# ESC2.net
KiCad netlist of a schematic drawn in Altium Designer
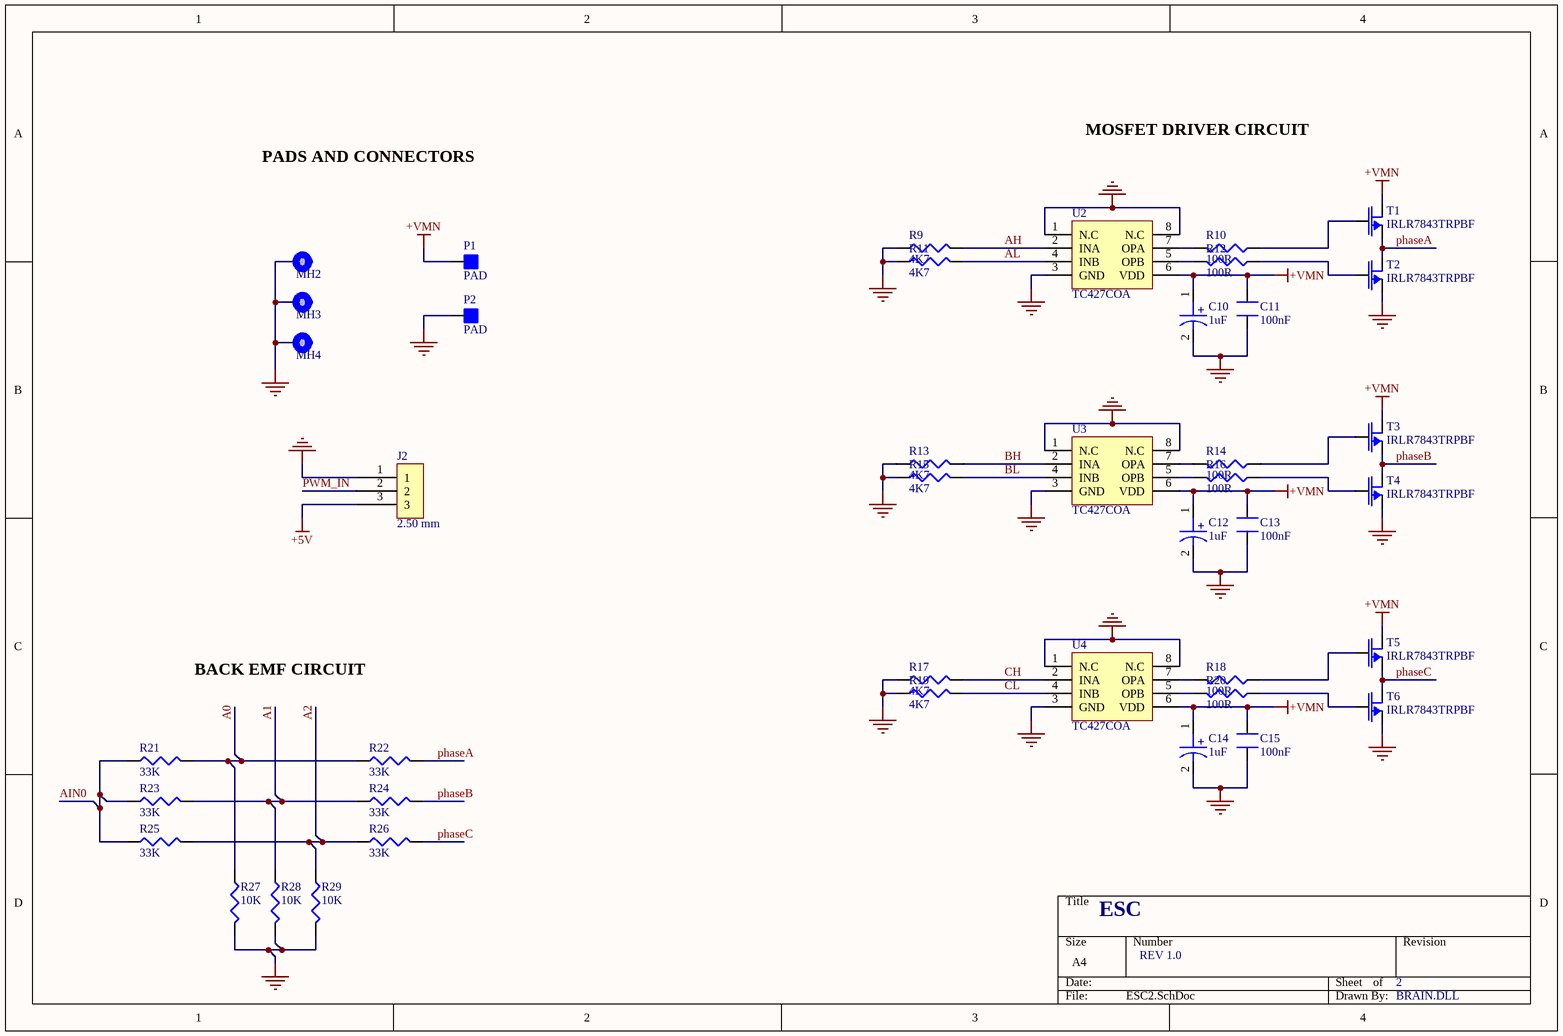
[diagram p0: ESC2.SchDoc]

(export (version "E")
  (design (tool "Eeschema 10.0.6"))
  (components
    (comp (ref "C10")
      (value "1uF")
      (footprint "1206 TANTAL CAP")
      (description "Cap Tant Solid 1uF 35V A CASE 10% (3.2 X 1.6 X 1.6mm) SMD 3216-18 7.5 Ohm 125 C T/R")
      (fields
        (field (name "MANUFACTURER") "KEMET")
        (field (name "MANUFACTURER PART NUMBER") "T491A105K035AT")
      )
      (libsource (lib "ESClib1") (part "T491A105K035AT"))
    )
    (comp (ref "C11")
      (value "100nF")
      (footprint "Z0603")
      (description "Multi Layer Ceramic Capacitor (MLCC) / Cap Ceramic 0.1uF 50V X7R 10% Pad SMD 0603 125°C T/R")
      (fields
        (field (name "MANUFACTURER") "Samsung")
        (field (name "MANUFACTURER PART NUMBER") "CL10B104KB8NNNC")
      )
      (libsource (lib "ESClib1") (part "CL10B104KB8NNNC"))
    )
    (comp (ref "C12")
      (value "1uF")
      (footprint "1206 TANTAL CAP")
      (description "Cap Tant Solid 1uF 35V A CASE 10% (3.2 X 1.6 X 1.6mm) SMD 3216-18 7.5 Ohm 125 C T/R")
      (fields
        (field (name "MANUFACTURER") "KEMET")
        (field (name "MANUFACTURER PART NUMBER") "T491A105K035AT")
      )
      (libsource (lib "ESClib1") (part "T491A105K035AT"))
    )
    (comp (ref "C13")
      (value "100nF")
      (footprint "Z0603")
      (description "Multi Layer Ceramic Capacitor (MLCC) / Cap Ceramic 0.1uF 50V X7R 10% Pad SMD 0603 125°C T/R")
      (fields
        (field (name "MANUFACTURER") "Samsung")
        (field (name "MANUFACTURER PART NUMBER") "CL10B104KB8NNNC")
      )
      (libsource (lib "ESClib1") (part "CL10B104KB8NNNC"))
    )
    (comp (ref "C14")
      (value "1uF")
      (footprint "1206 TANTAL CAP")
      (description "Cap Tant Solid 1uF 35V A CASE 10% (3.2 X 1.6 X 1.6mm) SMD 3216-18 7.5 Ohm 125 C T/R")
      (fields
        (field (name "MANUFACTURER") "KEMET")
        (field (name "MANUFACTURER PART NUMBER") "T491A105K035AT")
      )
      (libsource (lib "ESClib1") (part "T491A105K035AT"))
    )
    (comp (ref "C15")
      (value "100nF")
      (footprint "Z0603")
      (description "Multi Layer Ceramic Capacitor (MLCC) / Cap Ceramic 0.1uF 50V X7R 10% Pad SMD 0603 125°C T/R")
      (fields
        (field (name "MANUFACTURER") "Samsung")
        (field (name "MANUFACTURER PART NUMBER") "CL10B104KB8NNNC")
      )
      (libsource (lib "ESClib1") (part "CL10B104KB8NNNC"))
    )
    (comp (ref "J2")
      (value "2.50 mm")
      (footprint "L-KLS1-XL4-2.50-03-R")
      (libsource (lib "ESClib1") (part "L-KLS1-XL4-2.50-03-R"))
    )
    (comp (ref "MH2")
      (value "MH_7.4MMC_3.2MMD")
      (footprint "MH_7.4MMC_3.2MMD_NON_COPPER_NPLT")
      (description "Mounting Hole 7.4 mm Diameter (Non Copper), 3.2 mm Drill NPTH")
      (libsource (lib "ESClib1") (part "MH_7.4MMNC_3.2MMD"))
    )
    (comp (ref "MH3")
      (value "MH_7.4MMC_3.2MMD")
      (footprint "MH_7.4MMC_3.2MMD_NON_COPPER_NPLT")
      (description "Mounting Hole 7.4 mm Diameter (Non Copper), 3.2 mm Drill NPTH")
      (libsource (lib "ESClib1") (part "MH_7.4MMNC_3.2MMD"))
    )
    (comp (ref "MH4")
      (value "MH_7.4MMC_3.2MMD")
      (footprint "MH_7.4MMC_3.2MMD_NON_COPPER_NPLT")
      (description "Mounting Hole 7.4 mm Diameter (Non Copper), 3.2 mm Drill NPTH")
      (libsource (lib "ESClib1") (part "MH_7.4MMNC_3.2MMD"))
    )
    (comp (ref "P1") (value "PAD") (footprint "SQARE_PAD") (libsource (lib "ESClib1") (part "SQARE_PAD")))
    (comp (ref "P2") (value "PAD") (footprint "SQARE_PAD") (libsource (lib "ESClib1") (part "SQARE_PAD")))
    (comp (ref "R9")
      (value "4K7")
      (footprint "Z0603")
      (fields
        (field (name "MANUFACTURER") "Multicomp")
        (field (name "MANUFACTURER PART NUMBER") "MC0603SAF4701T5E")
        (field (name "TOLERANCE") "1%")
      )
      (libsource (lib "ESClib1") (part "MC0603SAF4701T5E"))
    )
    (comp (ref "R10") (value "100R") (footprint "Z0603") (libsource (lib "ESClib1") (part "0603SAJ0101T5E")))
    (comp (ref "R11")
      (value "4K7")
      (footprint "Z0603")
      (fields
        (field (name "MANUFACTURER") "Multicomp")
        (field (name "MANUFACTURER PART NUMBER") "MC0603SAF4701T5E")
        (field (name "TOLERANCE") "1%")
      )
      (libsource (lib "ESClib1") (part "MC0603SAF4701T5E"))
    )
    (comp (ref "R12") (value "100R") (footprint "Z0603") (libsource (lib "ESClib1") (part "0603SAJ0101T5E")))
    (comp (ref "R13")
      (value "4K7")
      (footprint "Z0603")
      (fields
        (field (name "MANUFACTURER") "Multicomp")
        (field (name "MANUFACTURER PART NUMBER") "MC0603SAF4701T5E")
        (field (name "TOLERANCE") "1%")
      )
      (libsource (lib "ESClib1") (part "MC0603SAF4701T5E"))
    )
    (comp (ref "R14") (value "100R") (footprint "Z0603") (libsource (lib "ESClib1") (part "0603SAJ0101T5E")))
    (comp (ref "R15")
      (value "4K7")
      (footprint "Z0603")
      (fields
        (field (name "MANUFACTURER") "Multicomp")
        (field (name "MANUFACTURER PART NUMBER") "MC0603SAF4701T5E")
        (field (name "TOLERANCE") "1%")
      )
      (libsource (lib "ESClib1") (part "MC0603SAF4701T5E"))
    )
    (comp (ref "R16") (value "100R") (footprint "Z0603") (libsource (lib "ESClib1") (part "0603SAJ0101T5E")))
    (comp (ref "R17")
      (value "4K7")
      (footprint "Z0603")
      (fields
        (field (name "MANUFACTURER") "Multicomp")
        (field (name "MANUFACTURER PART NUMBER") "MC0603SAF4701T5E")
        (field (name "TOLERANCE") "1%")
      )
      (libsource (lib "ESClib1") (part "MC0603SAF4701T5E"))
    )
    (comp (ref "R18") (value "100R") (footprint "Z0603") (libsource (lib "ESClib1") (part "0603SAJ0101T5E")))
    (comp (ref "R19")
      (value "4K7")
      (footprint "Z0603")
      (fields
        (field (name "MANUFACTURER") "Multicomp")
        (field (name "MANUFACTURER PART NUMBER") "MC0603SAF4701T5E")
        (field (name "TOLERANCE") "1%")
      )
      (libsource (lib "ESClib1") (part "MC0603SAF4701T5E"))
    )
    (comp (ref "R20") (value "100R") (footprint "Z0603") (libsource (lib "ESClib1") (part "0603SAJ0101T5E")))
    (comp (ref "R21") (value "33K") (footprint "Z0603") (libsource (lib "ESClib1") (part "RI0603L3302FT")))
    (comp (ref "R22") (value "33K") (footprint "Z0603") (libsource (lib "ESClib1") (part "RI0603L3302FT")))
    (comp (ref "R23") (value "33K") (footprint "Z0603") (libsource (lib "ESClib1") (part "RI0603L3302FT")))
    (comp (ref "R24") (value "33K") (footprint "Z0603") (libsource (lib "ESClib1") (part "RI0603L3302FT")))
    (comp (ref "R25") (value "33K") (footprint "Z0603") (libsource (lib "ESClib1") (part "RI0603L3302FT")))
    (comp (ref "R26") (value "33K") (footprint "Z0603") (libsource (lib "ESClib1") (part "RI0603L3302FT")))
    (comp (ref "R27") (value "10K") (footprint "Z0603") (libsource (lib "ESClib1") (part "CQ03SAF1002T5E")))
    (comp (ref "R28") (value "10K") (footprint "Z0603") (libsource (lib "ESClib1") (part "CQ03SAF1002T5E")))
    (comp (ref "R29") (value "10K") (footprint "Z0603") (libsource (lib "ESClib1") (part "CQ03SAF1002T5E")))
    (comp (ref "T1")
      (value "IRLR7843TRPBF")
      (footprint "TO-252-3")
      (description "MOSFET, 30V, 161A, 3.3 mOhm, 34 nC Qg, Logic Level, D-Pak")
      (fields (field (name "MANUFACTURER") "International Rectifier"))
      (libsource (lib "ESClib1") (part "IRLR7843TRPBF"))
    )
    (comp (ref "T2")
      (value "IRLR7843TRPBF")
      (footprint "TO-252-3")
      (description "MOSFET, 30V, 161A, 3.3 mOhm, 34 nC Qg, Logic Level, D-Pak")
      (fields (field (name "MANUFACTURER") "International Rectifier"))
      (libsource (lib "ESClib1") (part "IRLR7843TRPBF"))
    )
    (comp (ref "T3")
      (value "IRLR7843TRPBF")
      (footprint "TO-252-3")
      (description "MOSFET, 30V, 161A, 3.3 mOhm, 34 nC Qg, Logic Level, D-Pak")
      (fields (field (name "MANUFACTURER") "International Rectifier"))
      (libsource (lib "ESClib1") (part "IRLR7843TRPBF"))
    )
    (comp (ref "T4")
      (value "IRLR7843TRPBF")
      (footprint "TO-252-3")
      (description "MOSFET, 30V, 161A, 3.3 mOhm, 34 nC Qg, Logic Level, D-Pak")
      (fields (field (name "MANUFACTURER") "International Rectifier"))
      (libsource (lib "ESClib1") (part "IRLR7843TRPBF"))
    )
    (comp (ref "T5")
      (value "IRLR7843TRPBF")
      (footprint "TO-252-3")
      (description "MOSFET, 30V, 161A, 3.3 mOhm, 34 nC Qg, Logic Level, D-Pak")
      (fields (field (name "MANUFACTURER") "International Rectifier"))
      (libsource (lib "ESClib1") (part "IRLR7843TRPBF"))
    )
    (comp (ref "T6")
      (value "IRLR7843TRPBF")
      (footprint "TO-252-3")
      (description "MOSFET, 30V, 161A, 3.3 mOhm, 34 nC Qg, Logic Level, D-Pak")
      (fields (field (name "MANUFACTURER") "International Rectifier"))
      (libsource (lib "ESClib1") (part "IRLR7843TRPBF"))
    )
    (comp (ref "U2")
      (value "TC427COA")
      (footprint "SOIC-8")
      (description "IC MOSFET DVR 1.5A DUAL HS 8SOIC")
      (fields (field (name "MANUFACTURER") "Microchip"))
      (libsource (lib "ESClib1") (part "TC427COA"))
    )
    (comp (ref "U3")
      (value "TC427COA")
      (footprint "SOIC-8")
      (description "IC MOSFET DVR 1.5A DUAL HS 8SOIC")
      (fields (field (name "MANUFACTURER") "Microchip"))
      (libsource (lib "ESClib1") (part "TC427COA"))
    )
    (comp (ref "U4")
      (value "TC427COA")
      (footprint "SOIC-8")
      (description "IC MOSFET DVR 1.5A DUAL HS 8SOIC")
      (fields (field (name "MANUFACTURER") "Microchip"))
      (libsource (lib "ESClib1") (part "TC427COA"))
    )
  )
  (nets
    (net (code "1") (name "+5V") (class "Default")
      (node (ref "J2") (pin "3") (pinfunction "3_3") (pintype "passive"))
    )
    (net (code "2") (name "+VMN") (class "Default")
      (node (ref "C10") (pin "1") (pinfunction "1_1") (pintype "passive"))
      (node (ref "C11") (pin "1") (pinfunction "1_1") (pintype "passive"))
      (node (ref "C12") (pin "1") (pinfunction "1_1") (pintype "passive"))
      (node (ref "C13") (pin "1") (pinfunction "1_1") (pintype "passive"))
      (node (ref "C14") (pin "1") (pinfunction "1_1") (pintype "passive"))
      (node (ref "C15") (pin "1") (pinfunction "1_1") (pintype "passive"))
      (node (ref "P1") (pin "1") (pinfunction "1_1") (pintype "passive"))
      (node (ref "T1") (pin "2") (pinfunction "DRAIN_2") (pintype "passive"))
      (node (ref "T3") (pin "2") (pinfunction "DRAIN_2") (pintype "passive"))
      (node (ref "T5") (pin "2") (pinfunction "DRAIN_2") (pintype "passive"))
      (node (ref "U2") (pin "6") (pinfunction "VDD_6") (pintype "passive"))
      (node (ref "U3") (pin "6") (pinfunction "VDD_6") (pintype "passive"))
      (node (ref "U4") (pin "6") (pinfunction "VDD_6") (pintype "passive"))
    )
    (net (code "3") (name "/A0") (class "Default")
      (node (ref "R21") (pin "2") (pinfunction "2_2") (pintype "passive"))
      (node (ref "R22") (pin "1") (pinfunction "1_1") (pintype "passive"))
      (node (ref "R27") (pin "1") (pinfunction "1_1") (pintype "passive"))
    )
    (net (code "4") (name "/A1") (class "Default")
      (node (ref "R23") (pin "2") (pinfunction "2_2") (pintype "passive"))
      (node (ref "R24") (pin "1") (pinfunction "1_1") (pintype "passive"))
      (node (ref "R28") (pin "1") (pinfunction "1_1") (pintype "passive"))
    )
    (net (code "5") (name "/A2") (class "Default")
      (node (ref "R25") (pin "2") (pinfunction "2_2") (pintype "passive"))
      (node (ref "R26") (pin "1") (pinfunction "1_1") (pintype "passive"))
      (node (ref "R29") (pin "1") (pinfunction "1_1") (pintype "passive"))
    )
    (net (code "6") (name "/AH") (class "Default")
      (node (ref "R9") (pin "2") (pinfunction "2_2") (pintype "passive"))
      (node (ref "U2") (pin "2") (pinfunction "INA_2") (pintype "passive"))
    )
    (net (code "7") (name "/AIN0") (class "Default")
      (node (ref "R21") (pin "1") (pinfunction "1_1") (pintype "passive"))
      (node (ref "R23") (pin "1") (pinfunction "1_1") (pintype "passive"))
      (node (ref "R25") (pin "1") (pinfunction "1_1") (pintype "passive"))
    )
    (net (code "8") (name "/AL") (class "Default")
      (node (ref "R11") (pin "2") (pinfunction "2_2") (pintype "passive"))
      (node (ref "U2") (pin "4") (pinfunction "INB_4") (pintype "passive"))
    )
    (net (code "9") (name "/BH") (class "Default")
      (node (ref "R13") (pin "2") (pinfunction "2_2") (pintype "passive"))
      (node (ref "U3") (pin "2") (pinfunction "INA_2") (pintype "passive"))
    )
    (net (code "10") (name "/BL") (class "Default")
      (node (ref "R15") (pin "2") (pinfunction "2_2") (pintype "passive"))
      (node (ref "U3") (pin "4") (pinfunction "INB_4") (pintype "passive"))
    )
    (net (code "11") (name "/CH") (class "Default")
      (node (ref "R17") (pin "2") (pinfunction "2_2") (pintype "passive"))
      (node (ref "U4") (pin "2") (pinfunction "INA_2") (pintype "passive"))
    )
    (net (code "12") (name "/CL") (class "Default")
      (node (ref "R19") (pin "2") (pinfunction "2_2") (pintype "passive"))
      (node (ref "U4") (pin "4") (pinfunction "INB_4") (pintype "passive"))
    )
    (net (code "13") (name "/PWM_IN") (class "Default")
      (node (ref "J2") (pin "2") (pinfunction "2_2") (pintype "passive"))
    )
    (net (code "14") (name "/phaseA") (class "Default")
      (node (ref "R22") (pin "2") (pinfunction "2_2") (pintype "passive"))
      (node (ref "T1") (pin "3") (pinfunction "SOURCE_3") (pintype "passive"))
      (node (ref "T2") (pin "2") (pinfunction "DRAIN_2") (pintype "passive"))
    )
    (net (code "15") (name "/phaseB") (class "Default")
      (node (ref "R24") (pin "2") (pinfunction "2_2") (pintype "passive"))
      (node (ref "T3") (pin "3") (pinfunction "SOURCE_3") (pintype "passive"))
      (node (ref "T4") (pin "2") (pinfunction "DRAIN_2") (pintype "passive"))
    )
    (net (code "16") (name "/phaseC") (class "Default")
      (node (ref "R26") (pin "2") (pinfunction "2_2") (pintype "passive"))
      (node (ref "T5") (pin "3") (pinfunction "SOURCE_3") (pintype "passive"))
      (node (ref "T6") (pin "2") (pinfunction "DRAIN_2") (pintype "passive"))
    )
    (net (code "17") (name "GND") (class "Default")
      (node (ref "C10") (pin "2") (pinfunction "2_2") (pintype "passive"))
      (node (ref "C11") (pin "2") (pinfunction "2_2") (pintype "passive"))
      (node (ref "C12") (pin "2") (pinfunction "2_2") (pintype "passive"))
      (node (ref "C13") (pin "2") (pinfunction "2_2") (pintype "passive"))
      (node (ref "C14") (pin "2") (pinfunction "2_2") (pintype "passive"))
      (node (ref "C15") (pin "2") (pinfunction "2_2") (pintype "passive"))
      (node (ref "J2") (pin "1") (pinfunction "1_1") (pintype "passive"))
      (node (ref "MH2") (pin "1") (pinfunction "1_1") (pintype "passive"))
      (node (ref "MH3") (pin "1") (pinfunction "1_1") (pintype "passive"))
      (node (ref "MH4") (pin "1") (pinfunction "1_1") (pintype "passive"))
      (node (ref "P2") (pin "1") (pinfunction "1_1") (pintype "passive"))
      (node (ref "R11") (pin "1") (pinfunction "1_1") (pintype "passive"))
      (node (ref "R13") (pin "1") (pinfunction "1_1") (pintype "passive"))
      (node (ref "R15") (pin "1") (pinfunction "1_1") (pintype "passive"))
      (node (ref "R17") (pin "1") (pinfunction "1_1") (pintype "passive"))
      (node (ref "R19") (pin "1") (pinfunction "1_1") (pintype "passive"))
      (node (ref "R27") (pin "2") (pinfunction "2_2") (pintype "passive"))
      (node (ref "R28") (pin "2") (pinfunction "2_2") (pintype "passive"))
      (node (ref "R29") (pin "2") (pinfunction "2_2") (pintype "passive"))
      (node (ref "R9") (pin "1") (pinfunction "1_1") (pintype "passive"))
      (node (ref "T2") (pin "3") (pinfunction "SOURCE_3") (pintype "passive"))
      (node (ref "T4") (pin "3") (pinfunction "SOURCE_3") (pintype "passive"))
      (node (ref "T6") (pin "3") (pinfunction "SOURCE_3") (pintype "passive"))
      (node (ref "U2") (pin "1") (pinfunction "N.C_1") (pintype "passive"))
      (node (ref "U2") (pin "3") (pinfunction "GND_3") (pintype "passive"))
      (node (ref "U2") (pin "8") (pinfunction "N.C_8") (pintype "passive"))
      (node (ref "U3") (pin "1") (pinfunction "N.C_1") (pintype "passive"))
      (node (ref "U3") (pin "3") (pinfunction "GND_3") (pintype "passive"))
      (node (ref "U3") (pin "8") (pinfunction "N.C_8") (pintype "passive"))
      (node (ref "U4") (pin "1") (pinfunction "N.C_1") (pintype "passive"))
      (node (ref "U4") (pin "3") (pinfunction "GND_3") (pintype "passive"))
      (node (ref "U4") (pin "8") (pinfunction "N.C_8") (pintype "passive"))
    )
    (net (code "18") (name "Net-(T1-GATE)") (class "Default")
      (node (ref "R10") (pin "1") (pinfunction "1_1") (pintype "passive"))
      (node (ref "T1") (pin "1") (pinfunction "GATE_1") (pintype "passive"))
    )
    (net (code "19") (name "Net-(T2-GATE)") (class "Default")
      (node (ref "R12") (pin "1") (pinfunction "1_1") (pintype "passive"))
      (node (ref "T2") (pin "1") (pinfunction "GATE_1") (pintype "passive"))
    )
    (net (code "20") (name "Net-(T3-GATE)") (class "Default")
      (node (ref "R14") (pin "1") (pinfunction "1_1") (pintype "passive"))
      (node (ref "T3") (pin "1") (pinfunction "GATE_1") (pintype "passive"))
    )
    (net (code "21") (name "Net-(T4-GATE)") (class "Default")
      (node (ref "R16") (pin "1") (pinfunction "1_1") (pintype "passive"))
      (node (ref "T4") (pin "1") (pinfunction "GATE_1") (pintype "passive"))
    )
    (net (code "22") (name "Net-(T5-GATE)") (class "Default")
      (node (ref "R18") (pin "1") (pinfunction "1_1") (pintype "passive"))
      (node (ref "T5") (pin "1") (pinfunction "GATE_1") (pintype "passive"))
    )
    (net (code "23") (name "Net-(T6-GATE)") (class "Default")
      (node (ref "R20") (pin "1") (pinfunction "1_1") (pintype "passive"))
      (node (ref "T6") (pin "1") (pinfunction "GATE_1") (pintype "passive"))
    )
    (net (code "24") (name "Net-(U2-OPA)") (class "Default")
      (node (ref "R10") (pin "2") (pinfunction "2_2") (pintype "passive"))
      (node (ref "U2") (pin "7") (pinfunction "OPA_7") (pintype "passive"))
    )
    (net (code "25") (name "Net-(U2-OPB)") (class "Default")
      (node (ref "R12") (pin "2") (pinfunction "2_2") (pintype "passive"))
      (node (ref "U2") (pin "5") (pinfunction "OPB_5") (pintype "passive"))
    )
    (net (code "26") (name "Net-(U3-OPA)") (class "Default")
      (node (ref "R14") (pin "2") (pinfunction "2_2") (pintype "passive"))
      (node (ref "U3") (pin "7") (pinfunction "OPA_7") (pintype "passive"))
    )
    (net (code "27") (name "Net-(U3-OPB)") (class "Default")
      (node (ref "R16") (pin "2") (pinfunction "2_2") (pintype "passive"))
      (node (ref "U3") (pin "5") (pinfunction "OPB_5") (pintype "passive"))
    )
    (net (code "28") (name "Net-(U4-OPA)") (class "Default")
      (node (ref "R18") (pin "2") (pinfunction "2_2") (pintype "passive"))
      (node (ref "U4") (pin "7") (pinfunction "OPA_7") (pintype "passive"))
    )
    (net (code "29") (name "Net-(U4-OPB)") (class "Default")
      (node (ref "R20") (pin "2") (pinfunction "2_2") (pintype "passive"))
      (node (ref "U4") (pin "5") (pinfunction "OPB_5") (pintype "passive"))
    )
  )
)
